# design.net
KiCad netlist of a schematic drawn in Altium Designer
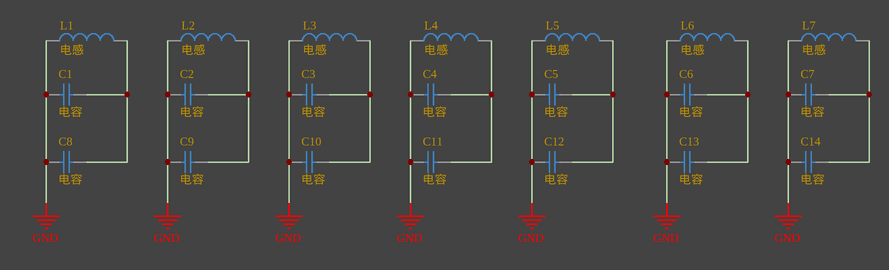
[diagram p0: 原理图.SchDoc]

(export (version "E")
  (design (tool "Eeschema 10.0.6"))
  (components
    (comp (ref "C1")
      (value "电容")
      (footprint "C0603")
      (description "Capacitor")
      (fields (field (name "PUBLISHER") "Altium Limited"))
      (libsource (lib "iMag") (part "电容"))
    )
    (comp (ref "C2")
      (value "电容")
      (footprint "C0603")
      (description "Capacitor")
      (fields (field (name "PUBLISHER") "Altium Limited"))
      (libsource (lib "iMag") (part "电容"))
    )
    (comp (ref "C3")
      (value "电容")
      (footprint "C0603")
      (description "Capacitor")
      (fields (field (name "PUBLISHER") "Altium Limited"))
      (libsource (lib "iMag") (part "电容"))
    )
    (comp (ref "C4")
      (value "电容")
      (footprint "C0603")
      (description "Capacitor")
      (fields (field (name "PUBLISHER") "Altium Limited"))
      (libsource (lib "iMag") (part "电容"))
    )
    (comp (ref "C5")
      (value "电容")
      (footprint "C0603")
      (description "Capacitor")
      (fields (field (name "PUBLISHER") "Altium Limited"))
      (libsource (lib "iMag") (part "电容"))
    )
    (comp (ref "C6")
      (value "电容")
      (footprint "C0603")
      (description "Capacitor")
      (fields (field (name "PUBLISHER") "Altium Limited"))
      (libsource (lib "iMag") (part "电容"))
    )
    (comp (ref "C7")
      (value "电容")
      (footprint "C0603")
      (description "Capacitor")
      (fields (field (name "PUBLISHER") "Altium Limited"))
      (libsource (lib "iMag") (part "电容"))
    )
    (comp (ref "C8")
      (value "电容")
      (footprint "C0603")
      (description "Capacitor")
      (fields (field (name "PUBLISHER") "Altium Limited"))
      (libsource (lib "iMag") (part "电容"))
    )
    (comp (ref "C9")
      (value "电容")
      (footprint "C0603")
      (description "Capacitor")
      (fields (field (name "PUBLISHER") "Altium Limited"))
      (libsource (lib "iMag") (part "电容"))
    )
    (comp (ref "C10")
      (value "电容")
      (footprint "C0603")
      (description "Capacitor")
      (fields (field (name "PUBLISHER") "Altium Limited"))
      (libsource (lib "iMag") (part "电容"))
    )
    (comp (ref "C11")
      (value "电容")
      (footprint "C0603")
      (description "Capacitor")
      (fields (field (name "PUBLISHER") "Altium Limited"))
      (libsource (lib "iMag") (part "电容"))
    )
    (comp (ref "C12")
      (value "电容")
      (footprint "C0603")
      (description "Capacitor")
      (fields (field (name "PUBLISHER") "Altium Limited"))
      (libsource (lib "iMag") (part "电容"))
    )
    (comp (ref "C13")
      (value "电容")
      (footprint "C0603")
      (description "Capacitor")
      (fields (field (name "PUBLISHER") "Altium Limited"))
      (libsource (lib "iMag") (part "电容"))
    )
    (comp (ref "C14")
      (value "电容")
      (footprint "C0603")
      (description "Capacitor")
      (fields (field (name "PUBLISHER") "Altium Limited"))
      (libsource (lib "iMag") (part "电容"))
    )
    (comp (ref "L1") (value "电感") (footprint "LD8x10") (libsource (lib "iMag") (part "电感")))
    (comp (ref "L2") (value "电感") (footprint "LD8x10") (libsource (lib "iMag") (part "电感")))
    (comp (ref "L3") (value "电感") (footprint "LD8x10") (libsource (lib "iMag") (part "电感")))
    (comp (ref "L4") (value "电感") (footprint "LD8x10") (libsource (lib "iMag") (part "电感")))
    (comp (ref "L5") (value "电感") (footprint "LD8x10") (libsource (lib "iMag") (part "电感")))
    (comp (ref "L6") (value "电感") (footprint "LD8x10") (libsource (lib "iMag") (part "电感")))
    (comp (ref "L7") (value "电感") (footprint "LD8x10") (libsource (lib "iMag") (part "电感")))
  )
  (nets
    (net (code "1") (name "GND") (class "Default")
      (node (ref "C1") (pin "1") (pinfunction "1_1") (pintype "passive"))
      (node (ref "C10") (pin "1") (pinfunction "1_1") (pintype "passive"))
      (node (ref "C11") (pin "1") (pinfunction "1_1") (pintype "passive"))
      (node (ref "C12") (pin "1") (pinfunction "1_1") (pintype "passive"))
      (node (ref "C13") (pin "1") (pinfunction "1_1") (pintype "passive"))
      (node (ref "C14") (pin "1") (pinfunction "1_1") (pintype "passive"))
      (node (ref "C2") (pin "1") (pinfunction "1_1") (pintype "passive"))
      (node (ref "C3") (pin "1") (pinfunction "1_1") (pintype "passive"))
      (node (ref "C4") (pin "1") (pinfunction "1_1") (pintype "passive"))
      (node (ref "C5") (pin "1") (pinfunction "1_1") (pintype "passive"))
      (node (ref "C6") (pin "1") (pinfunction "1_1") (pintype "passive"))
      (node (ref "C7") (pin "1") (pinfunction "1_1") (pintype "passive"))
      (node (ref "C8") (pin "1") (pinfunction "1_1") (pintype "passive"))
      (node (ref "C9") (pin "1") (pinfunction "1_1") (pintype "passive"))
      (node (ref "L1") (pin "1") (pinfunction "1_1") (pintype "passive"))
      (node (ref "L2") (pin "1") (pinfunction "1_1") (pintype "passive"))
      (node (ref "L3") (pin "1") (pinfunction "1_1") (pintype "passive"))
      (node (ref "L4") (pin "1") (pinfunction "1_1") (pintype "passive"))
      (node (ref "L5") (pin "1") (pinfunction "1_1") (pintype "passive"))
      (node (ref "L6") (pin "1") (pinfunction "1_1") (pintype "passive"))
      (node (ref "L7") (pin "1") (pinfunction "1_1") (pintype "passive"))
    )
    (net (code "2") (name "Net-(C1-Pad2)") (class "Default")
      (node (ref "C1") (pin "2") (pinfunction "2_2") (pintype "passive"))
      (node (ref "C8") (pin "2") (pinfunction "2_2") (pintype "passive"))
      (node (ref "L1") (pin "2") (pinfunction "2_2") (pintype "passive"))
    )
    (net (code "3") (name "Net-(C2-Pad2)") (class "Default")
      (node (ref "C2") (pin "2") (pinfunction "2_2") (pintype "passive"))
      (node (ref "C9") (pin "2") (pinfunction "2_2") (pintype "passive"))
      (node (ref "L2") (pin "2") (pinfunction "2_2") (pintype "passive"))
    )
    (net (code "4") (name "Net-(C10-Pad2)") (class "Default")
      (node (ref "C10") (pin "2") (pinfunction "2_2") (pintype "passive"))
      (node (ref "C3") (pin "2") (pinfunction "2_2") (pintype "passive"))
      (node (ref "L3") (pin "2") (pinfunction "2_2") (pintype "passive"))
    )
    (net (code "5") (name "Net-(C11-Pad2)") (class "Default")
      (node (ref "C11") (pin "2") (pinfunction "2_2") (pintype "passive"))
      (node (ref "C4") (pin "2") (pinfunction "2_2") (pintype "passive"))
      (node (ref "L4") (pin "2") (pinfunction "2_2") (pintype "passive"))
    )
    (net (code "6") (name "Net-(C12-Pad2)") (class "Default")
      (node (ref "C12") (pin "2") (pinfunction "2_2") (pintype "passive"))
      (node (ref "C5") (pin "2") (pinfunction "2_2") (pintype "passive"))
      (node (ref "L5") (pin "2") (pinfunction "2_2") (pintype "passive"))
    )
    (net (code "7") (name "Net-(C13-Pad2)") (class "Default")
      (node (ref "C13") (pin "2") (pinfunction "2_2") (pintype "passive"))
      (node (ref "C6") (pin "2") (pinfunction "2_2") (pintype "passive"))
      (node (ref "L6") (pin "2") (pinfunction "2_2") (pintype "passive"))
    )
    (net (code "8") (name "Net-(C14-Pad2)") (class "Default")
      (node (ref "C14") (pin "2") (pinfunction "2_2") (pintype "passive"))
      (node (ref "C7") (pin "2") (pinfunction "2_2") (pintype "passive"))
      (node (ref "L7") (pin "2") (pinfunction "2_2") (pintype "passive"))
    )
  )
)
